# PJ20.net
KiCad netlist of a schematic drawn in EAGLE
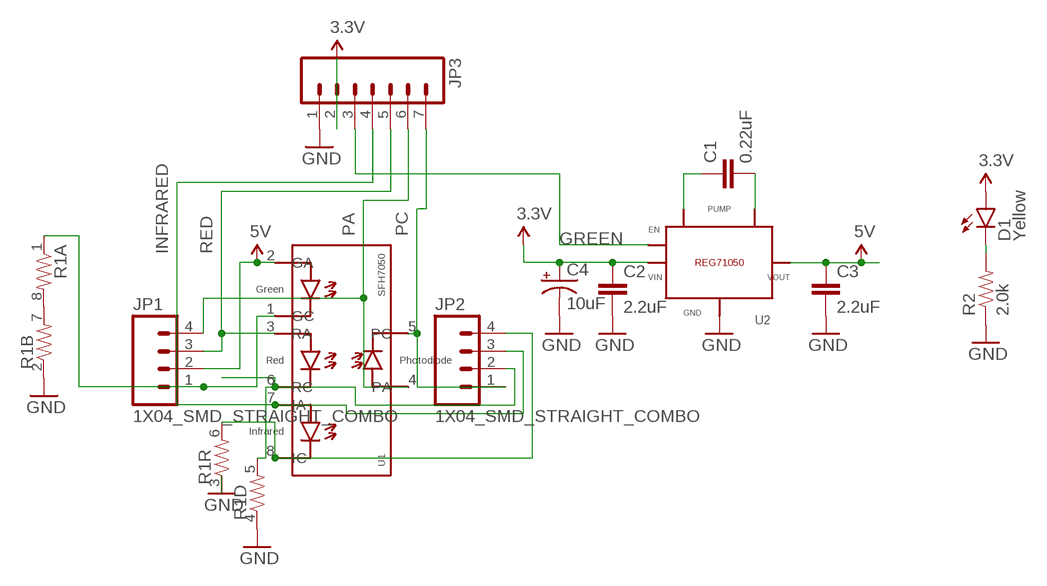
[diagram p0: schematic, sheet 1]

(export (version "E")
  (design (tool "Eeschema 10.0.6"))
  (components
    (comp (ref "C1")
      (value "0.22uF")
      (footprint "eagle-import:0603-CAP")
      (libsource (lib "eagle-import") (part "0.22UF-25V-10%(0603)"))
    )
    (comp (ref "C2")
      (value "2.2uF")
      (footprint "eagle-import:0805-CAP")
      (libsource (lib "eagle-import") (part "2.2UF-25V-+80/-20(0805)"))
    )
    (comp (ref "C3")
      (value "2.2uF")
      (footprint "eagle-import:0805-CAP")
      (libsource (lib "eagle-import") (part "2.2UF-25V-+80/-20(0805)"))
    )
    (comp (ref "C4")
      (value "10uF")
      (footprint "eagle-import:EIA3216")
      (libsource (lib "eagle-import") (part "10UF-16V-10%(TANT)"))
    )
    (comp (ref "D1")
      (value "Yellow")
      (footprint "eagle-import:LED-0603")
      (libsource (lib "eagle-import") (part "LED-YELLOW0603"))
    )
    (comp (ref "JP1")
      (value "1X04_SMD_STRAIGHT_COMBO")
      (footprint "eagle-import:1X04_SMD_STRAIGHT_COMBO")
      (libsource (lib "eagle-import") (part "M04SMD_STRAIGHT_COMBO"))
    )
    (comp (ref "JP2")
      (value "1X04_SMD_STRAIGHT_COMBO")
      (footprint "eagle-import:1X04_SMD_STRAIGHT_COMBO")
      (libsource (lib "eagle-import") (part "M04SMD_STRAIGHT_COMBO"))
    )
    (comp (ref "JP3")
      (value "M07LOCK")
      (footprint "eagle-import:1X07_LOCK")
      (libsource (lib "eagle-import") (part "M07LOCK"))
    )
    (comp (ref "R1")
      (value "RESISTOR-ARRAY0603-ARV")
      (footprint "eagle-import:0603-ARV")
      (libsource (lib "eagle-import") (part "RESISTOR-ARRAY0603-ARV"))
    )
    (comp (ref "R2")
      (value "2.0k")
      (footprint "eagle-import:0603-RES")
      (libsource (lib "eagle-import") (part "2.0KOHM1/10W5%(0603)"))
    )
    (comp (ref "U1")
      (value "SFH7050")
      (footprint "eagle-import:SFH7050")
      (libsource (lib "eagle-import") (part "SFH7050"))
    )
    (comp (ref "U2")
      (value "REG71050")
      (footprint "eagle-import:DDC")
      (libsource (lib "eagle-import") (part "REG71050"))
    )
  )
  (nets
    (net (code "1") (name "/GREEN") (class "Default")
      (node (ref "JP3") (pin "3") (pinfunction "3_3") (pintype "passive"))
      (node (ref "U2") (pin "3") (pinfunction "ENABLE_3") (pintype "bidirectional"))
    )
    (net (code "2") (name "/INFRARED") (class "Default")
      (node (ref "JP2") (pin "3") (pinfunction "3_3") (pintype "passive"))
      (node (ref "JP3") (pin "4") (pinfunction "4_4") (pintype "passive"))
      (node (ref "U1") (pin "7") (pinfunction "IA_7") (pintype "bidirectional"))
    )
    (net (code "3") (name "/PA") (class "Default")
      (node (ref "JP1") (pin "4") (pinfunction "4_4") (pintype "passive"))
      (node (ref "JP3") (pin "6") (pinfunction "6_6") (pintype "passive"))
      (node (ref "U1") (pin "4") (pinfunction "PA_4") (pintype "bidirectional"))
    )
    (net (code "4") (name "/PC") (class "Default")
      (node (ref "JP2") (pin "1") (pinfunction "1_1") (pintype "passive"))
      (node (ref "JP3") (pin "7") (pinfunction "7_7") (pintype "passive"))
      (node (ref "U1") (pin "5") (pinfunction "PC_5") (pintype "bidirectional"))
    )
    (net (code "5") (name "/RED") (class "Default")
      (node (ref "JP1") (pin "3") (pinfunction "3_3") (pintype "passive"))
      (node (ref "JP3") (pin "5") (pinfunction "5_5") (pintype "passive"))
      (node (ref "U1") (pin "3") (pinfunction "RA_3") (pintype "bidirectional"))
    )
    (net (code "6") (name "3.3V") (class "Default")
      (node (ref "C2") (pin "1") (pinfunction "1_1") (pintype "passive"))
      (node (ref "C4") (pin "A") (pinfunction "+_A") (pintype "passive"))
      (node (ref "D1") (pin "A") (pinfunction "A_A") (pintype "passive"))
      (node (ref "JP3") (pin "2") (pinfunction "2_2") (pintype "passive"))
      (node (ref "U2") (pin "5") (pinfunction "VIN_5") (pintype "bidirectional"))
    )
    (net (code "7") (name "5V") (class "Default")
      (node (ref "C3") (pin "1") (pinfunction "1_1") (pintype "passive"))
      (node (ref "JP1") (pin "2") (pinfunction "2_2") (pintype "passive"))
      (node (ref "U1") (pin "2") (pinfunction "GA_2") (pintype "bidirectional"))
      (node (ref "U2") (pin "1") (pinfunction "VOUT_1") (pintype "bidirectional"))
    )
    (net (code "8") (name "GND") (class "Default")
      (node (ref "C2") (pin "2") (pinfunction "2_2") (pintype "passive"))
      (node (ref "C3") (pin "2") (pinfunction "2_2") (pintype "passive"))
      (node (ref "C4") (pin "C") (pinfunction "-_C") (pintype "passive"))
      (node (ref "JP3") (pin "1") (pinfunction "1_1") (pintype "passive"))
      (node (ref "R1") (pin "2") (pinfunction "1_2") (pintype "passive"))
      (node (ref "R1") (pin "3") (pinfunction "1_3") (pintype "passive"))
      (node (ref "R1") (pin "4") (pinfunction "1_4") (pintype "passive"))
      (node (ref "R2") (pin "1") (pinfunction "1_1") (pintype "passive"))
      (node (ref "U2") (pin "2") (pinfunction "GND_2") (pintype "bidirectional"))
    )
    (net (code "9") (name "Net-(D1-PadC)") (class "Default")
      (node (ref "D1") (pin "C") (pinfunction "C_C") (pintype "passive"))
      (node (ref "R2") (pin "2") (pinfunction "2_2") (pintype "passive"))
    )
    (net (code "10") (name "Net-(R1A-2)") (class "Default")
      (node (ref "R1") (pin "7") (pinfunction "2_7") (pintype "passive"))
      (node (ref "R1") (pin "8") (pinfunction "2_8") (pintype "passive"))
    )
    (net (code "11") (name "Net-(R1C-2)") (class "Default")
      (node (ref "JP2") (pin "2") (pinfunction "2_2") (pintype "passive"))
      (node (ref "R1") (pin "5") (pinfunction "2_5") (pintype "passive"))
      (node (ref "U1") (pin "6") (pinfunction "RC_6") (pintype "bidirectional"))
    )
    (net (code "12") (name "Net-(R1D-2)") (class "Default")
      (node (ref "JP2") (pin "4") (pinfunction "4_4") (pintype "passive"))
      (node (ref "R1") (pin "6") (pinfunction "2_6") (pintype "passive"))
      (node (ref "U1") (pin "8") (pinfunction "IC_8") (pintype "bidirectional"))
    )
    (net (code "13") (name "Net-(U1-GC)") (class "Default")
      (node (ref "JP1") (pin "1") (pinfunction "1_1") (pintype "passive"))
      (node (ref "R1") (pin "1") (pinfunction "1_1") (pintype "passive"))
      (node (ref "U1") (pin "1") (pinfunction "GC_1") (pintype "bidirectional"))
    )
    (net (code "14") (name "Net-(U2-CPUMP+)") (class "Default")
      (node (ref "C1") (pin "2") (pinfunction "2_2") (pintype "passive"))
      (node (ref "U2") (pin "6") (pinfunction "CPUMP+_6") (pintype "bidirectional"))
    )
    (net (code "15") (name "Net-(U2-CPUMP-)") (class "Default")
      (node (ref "C1") (pin "1") (pinfunction "1_1") (pintype "passive"))
      (node (ref "U2") (pin "4") (pinfunction "CPUMP-_4") (pintype "bidirectional"))
    )
  )
)
